# ibdtia.net
KiCad netlist of a schematic drawn in EAGLE
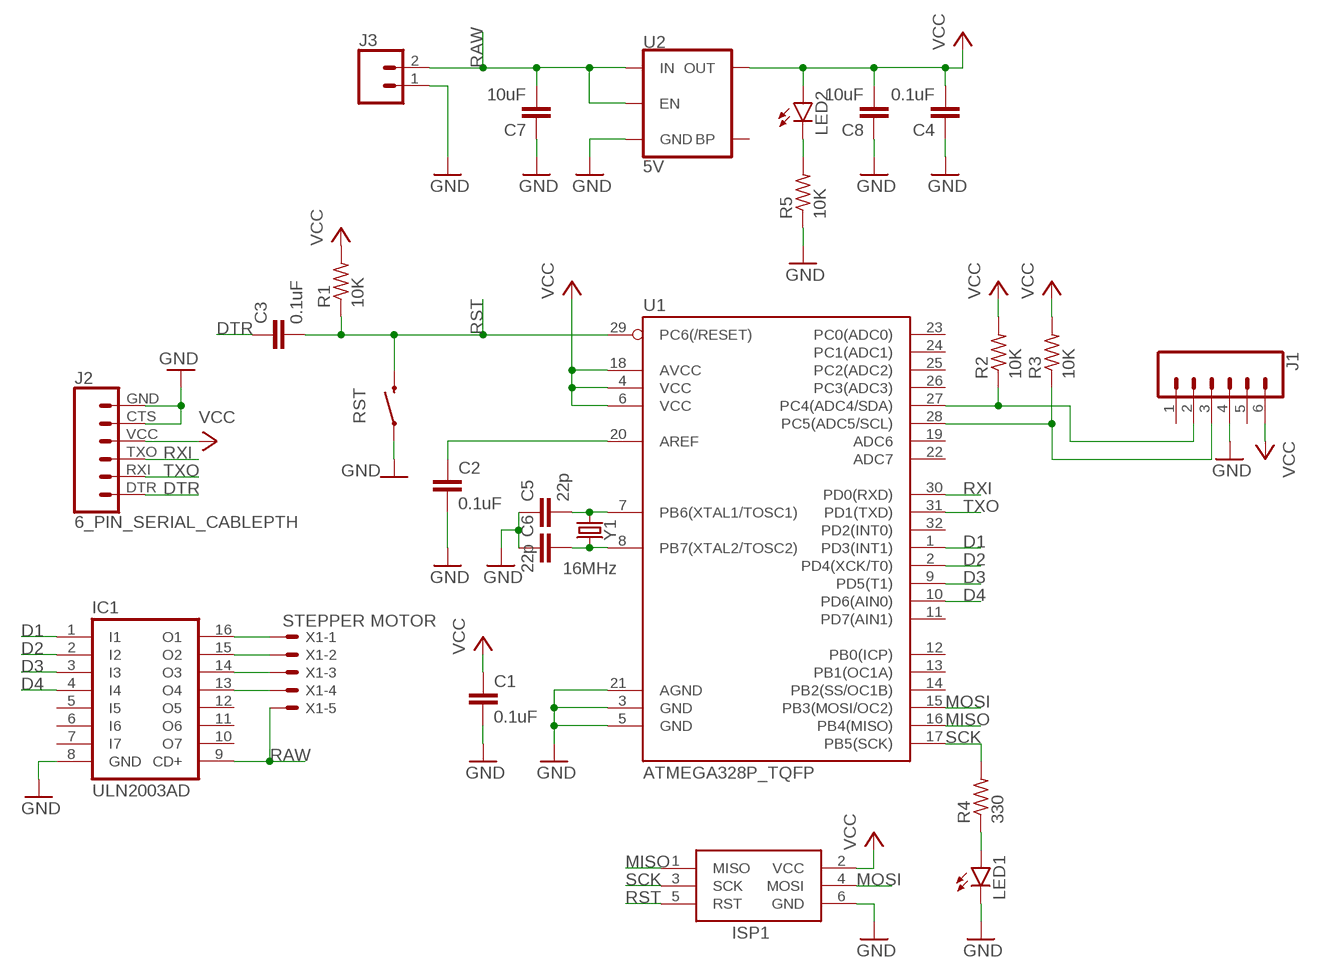
[diagram p0: schematic, sheet 1]

(export (version "E")
  (design (tool "Eeschema 10.0.6"))
  (components
    (comp (ref "C1")
      (value "0.1uF")
      (footprint "eagle-import:C0805")
      (libsource (lib "eagle-import") (part "C-EUC0805"))
    )
    (comp (ref "C2")
      (value "0.1uF")
      (footprint "eagle-import:C0805")
      (libsource (lib "eagle-import") (part "C-EUC0805"))
    )
    (comp (ref "C3")
      (value "0.1uF")
      (footprint "eagle-import:C0805")
      (libsource (lib "eagle-import") (part "C-EUC0805"))
    )
    (comp (ref "C4")
      (value "0.1uF")
      (footprint "eagle-import:C0805")
      (libsource (lib "eagle-import") (part "C-EUC0805"))
    )
    (comp (ref "C5")
      (value "22p")
      (footprint "eagle-import:C0805")
      (libsource (lib "eagle-import") (part "C-EUC0805"))
    )
    (comp (ref "C6")
      (value "22p")
      (footprint "eagle-import:C0805")
      (libsource (lib "eagle-import") (part "C-EUC0805"))
    )
    (comp (ref "C7")
      (value "10uF")
      (footprint "eagle-import:C0805")
      (libsource (lib "eagle-import") (part "C-EUC0805"))
    )
    (comp (ref "C8")
      (value "10uF")
      (footprint "eagle-import:C0805")
      (libsource (lib "eagle-import") (part "C-EUC0805"))
    )
    (comp (ref "IC1")
      (value "ULN2003AD")
      (footprint "eagle-import:SO16")
      (libsource (lib "eagle-import") (part "ULN2003AD"))
    )
    (comp (ref "ISP1")
      (value "AVRISP-6")
      (footprint "eagle-import:AVRISP")
      (libsource (lib "eagle-import") (part "AVRISP-6"))
    )
    (comp (ref "J1")
      (value "CONN_06NO_SILK_FEMALE_PTH")
      (footprint "eagle-import:1X06_NO_SILK")
      (libsource (lib "eagle-import") (part "CONN_06NO_SILK_FEMALE_PTH"))
    )
    (comp (ref "J2")
      (value "6_PIN_SERIAL_CABLEPTH")
      (footprint "eagle-import:FTDI_BASIC")
      (libsource (lib "eagle-import") (part "6_PIN_SERIAL_CABLEPTH"))
    )
    (comp (ref "J3")
      (value "CONN_02")
      (footprint "eagle-import:1X02")
      (libsource (lib "eagle-import") (part "CONN_02"))
    )
    (comp (ref "LED1")
      (value "LEDCHIP-LED0805")
      (footprint "eagle-import:CHIP-LED0805")
      (libsource (lib "eagle-import") (part "LEDCHIP-LED0805"))
    )
    (comp (ref "LED2")
      (value "LEDCHIP-LED0805")
      (footprint "eagle-import:CHIP-LED0805")
      (libsource (lib "eagle-import") (part "LEDCHIP-LED0805"))
    )
    (comp (ref "R1")
      (value "10K")
      (footprint "eagle-import:R0805")
      (libsource (lib "eagle-import") (part "R-US_R0805"))
    )
    (comp (ref "R2")
      (value "10K")
      (footprint "eagle-import:R0805")
      (libsource (lib "eagle-import") (part "R-US_R0805"))
    )
    (comp (ref "R3")
      (value "10K")
      (footprint "eagle-import:R0805")
      (libsource (lib "eagle-import") (part "R-US_R0805"))
    )
    (comp (ref "R4")
      (value "330")
      (footprint "eagle-import:R0805")
      (libsource (lib "eagle-import") (part "R-US_R0805"))
    )
    (comp (ref "R5")
      (value "10K")
      (footprint "eagle-import:R0805")
      (libsource (lib "eagle-import") (part "R-US_R0805"))
    )
    (comp (ref "RST")
      (value "MOMENTARY-SWITCH-SPST-SMD-4.5MM")
      (footprint "eagle-import:TACTILE_SWITCH_SMD_4.5MM")
      (libsource (lib "eagle-import") (part "MOMENTARY-SWITCH-SPST-SMD-4.5MM"))
    )
    (comp (ref "U1")
      (value "ATMEGA328P_TQFP")
      (footprint "eagle-import:TQFP32-08")
      (libsource (lib "eagle-import") (part "ATMEGA328P_TQFP"))
    )
    (comp (ref "U2")
      (value "5V")
      (footprint "eagle-import:SOT23-5")
      (libsource (lib "eagle-import") (part "V_REG_MIC52055V"))
    )
    (comp (ref "X1")
      (value "STEPPER MOTOR")
      (footprint "eagle-import:JST-XH-05-PACKAGE-ROUND-PAD")
      (libsource (lib "eagle-import") (part "JST-XH-05-PIN-ROUND-PAD"))
    )
    (comp (ref "Y1")
      (value "16MHz")
      (footprint "eagle-import:CRYSTAL-SMD-5X3.2-4PAD")
      (libsource (lib "eagle-import") (part "CRYSTAL-16MHZSMD-5X3.2"))
    )
  )
  (nets
    (net (code "1") (name "/D1") (class "Default")
      (node (ref "IC1") (pin "1") (pinfunction "I1_1") (pintype "input"))
      (node (ref "U1") (pin "1") (pinfunction "PD3(INT1)_1") (pintype "bidirectional"))
    )
    (net (code "2") (name "/D2") (class "Default")
      (node (ref "IC1") (pin "2") (pinfunction "I2_2") (pintype "input"))
      (node (ref "U1") (pin "2") (pinfunction "PD4(XCK/T0)_2") (pintype "bidirectional"))
    )
    (net (code "3") (name "/D3") (class "Default")
      (node (ref "IC1") (pin "3") (pinfunction "I3_3") (pintype "input"))
      (node (ref "U1") (pin "9") (pinfunction "PD5(T1)_9") (pintype "bidirectional"))
    )
    (net (code "4") (name "/D4") (class "Default")
      (node (ref "IC1") (pin "4") (pinfunction "I4_4") (pintype "input"))
      (node (ref "U1") (pin "10") (pinfunction "PD6(AIN0)_10") (pintype "bidirectional"))
    )
    (net (code "5") (name "/DTR") (class "Default")
      (node (ref "C3") (pin "1") (pinfunction "1_1") (pintype "passive"))
      (node (ref "J2") (pin "DTR") (pinfunction "1_DTR") (pintype "passive"))
    )
    (net (code "6") (name "/MISO") (class "Default")
      (node (ref "ISP1") (pin "1") (pinfunction "MISO_1") (pintype "input"))
      (node (ref "U1") (pin "16") (pinfunction "PB4(MISO)_16") (pintype "bidirectional"))
    )
    (net (code "7") (name "/MOSI") (class "Default")
      (node (ref "ISP1") (pin "4") (pinfunction "MOSI_4") (pintype "output"))
      (node (ref "U1") (pin "15") (pinfunction "PB3(MOSI/OC2)_15") (pintype "bidirectional"))
    )
    (net (code "8") (name "/RAW") (class "Default")
      (node (ref "C7") (pin "2") (pinfunction "2_2") (pintype "passive"))
      (node (ref "IC1") (pin "9") (pinfunction "CD+_9") (pintype "passive"))
      (node (ref "J3") (pin "2") (pinfunction "2_2") (pintype "passive"))
      (node (ref "U2") (pin "1") (pinfunction "IN_1") (pintype "input"))
      (node (ref "U2") (pin "3") (pinfunction "EN_3") (pintype "input"))
      (node (ref "X1") (pin "5") (pinfunction "S_5") (pintype "passive"))
    )
    (net (code "9") (name "/RST") (class "Default")
      (node (ref "C3") (pin "2") (pinfunction "2_2") (pintype "passive"))
      (node (ref "ISP1") (pin "5") (pinfunction "RST_5") (pintype "output"))
      (node (ref "R1") (pin "1") (pinfunction "1_1") (pintype "passive"))
      (node (ref "RST") (pin "1") (pinfunction "2_1") (pintype "passive"))
      (node (ref "RST") (pin "4") (pinfunction "2_4") (pintype "passive"))
      (node (ref "U1") (pin "29") (pinfunction "PC6(/RESET)_29") (pintype "bidirectional"))
    )
    (net (code "10") (name "/RXI") (class "Default")
      (node (ref "J2") (pin "TXO") (pinfunction "3_TXO") (pintype "passive"))
      (node (ref "U1") (pin "30") (pinfunction "PD0(RXD)_30") (pintype "bidirectional"))
    )
    (net (code "11") (name "/SCK") (class "Default")
      (node (ref "ISP1") (pin "3") (pinfunction "SCK_3") (pintype "output"))
      (node (ref "R4") (pin "2") (pinfunction "2_2") (pintype "passive"))
      (node (ref "U1") (pin "17") (pinfunction "PB5(SCK)_17") (pintype "bidirectional"))
    )
    (net (code "12") (name "/TXO") (class "Default")
      (node (ref "J2") (pin "RXI") (pinfunction "2_RXI") (pintype "passive"))
      (node (ref "U1") (pin "31") (pinfunction "PD1(TXD)_31") (pintype "bidirectional"))
    )
    (net (code "13") (name "GND") (class "Default")
      (node (ref "C1") (pin "2") (pinfunction "2_2") (pintype "passive"))
      (node (ref "C2") (pin "2") (pinfunction "2_2") (pintype "passive"))
      (node (ref "C4") (pin "1") (pinfunction "1_1") (pintype "passive"))
      (node (ref "C5") (pin "1") (pinfunction "1_1") (pintype "passive"))
      (node (ref "C6") (pin "1") (pinfunction "1_1") (pintype "passive"))
      (node (ref "C7") (pin "1") (pinfunction "1_1") (pintype "passive"))
      (node (ref "C8") (pin "1") (pinfunction "1_1") (pintype "passive"))
      (node (ref "IC1") (pin "8") (pinfunction "GND_8") (pintype "power_in"))
      (node (ref "ISP1") (pin "6") (pinfunction "GND_6") (pintype "power_in"))
      (node (ref "J1") (pin "4") (pinfunction "4_4") (pintype "passive"))
      (node (ref "J2") (pin "CTS") (pinfunction "5_CTS") (pintype "passive"))
      (node (ref "J2") (pin "GND") (pinfunction "6_GND") (pintype "passive"))
      (node (ref "J3") (pin "1") (pinfunction "1_1") (pintype "passive"))
      (node (ref "LED1") (pin "C") (pinfunction "C_C") (pintype "passive"))
      (node (ref "R5") (pin "1") (pinfunction "1_1") (pintype "passive"))
      (node (ref "RST") (pin "2") (pinfunction "1_2") (pintype "passive"))
      (node (ref "RST") (pin "3") (pinfunction "1_3") (pintype "passive"))
      (node (ref "U1") (pin "21") (pinfunction "AGND_21") (pintype "bidirectional"))
      (node (ref "U1") (pin "3") (pinfunction "GND_3") (pintype "bidirectional"))
      (node (ref "U1") (pin "5") (pinfunction "GND_5") (pintype "bidirectional"))
      (node (ref "U2") (pin "2") (pinfunction "GND_2") (pintype "input"))
    )
    (net (code "14") (name "Net-(IC1-O1)") (class "Default")
      (node (ref "IC1") (pin "16") (pinfunction "O1_16") (pintype "open_collector"))
      (node (ref "X1") (pin "1") (pinfunction "S_1") (pintype "passive"))
    )
    (net (code "15") (name "Net-(IC1-O2)") (class "Default")
      (node (ref "IC1") (pin "15") (pinfunction "O2_15") (pintype "open_collector"))
      (node (ref "X1") (pin "2") (pinfunction "S_2") (pintype "passive"))
    )
    (net (code "16") (name "Net-(IC1-O3)") (class "Default")
      (node (ref "IC1") (pin "14") (pinfunction "O3_14") (pintype "open_collector"))
      (node (ref "X1") (pin "3") (pinfunction "S_3") (pintype "passive"))
    )
    (net (code "17") (name "Net-(IC1-O4)") (class "Default")
      (node (ref "IC1") (pin "13") (pinfunction "O4_13") (pintype "open_collector"))
      (node (ref "X1") (pin "4") (pinfunction "S_4") (pintype "passive"))
    )
    (net (code "18") (name "Net-(LED1-PadA)") (class "Default")
      (node (ref "LED1") (pin "A") (pinfunction "A_A") (pintype "passive"))
      (node (ref "R4") (pin "1") (pinfunction "1_1") (pintype "passive"))
    )
    (net (code "19") (name "Net-(LED2-PadC)") (class "Default")
      (node (ref "LED2") (pin "C") (pinfunction "C_C") (pintype "passive"))
      (node (ref "R5") (pin "2") (pinfunction "2_2") (pintype "passive"))
    )
    (net (code "20") (name "Net-(U1-AREF)") (class "Default")
      (node (ref "C2") (pin "1") (pinfunction "1_1") (pintype "passive"))
      (node (ref "U1") (pin "20") (pinfunction "AREF_20") (pintype "bidirectional"))
    )
    (net (code "21") (name "Net-(U1-PB6(XTAL1{slash}TOSC1))") (class "Default")
      (node (ref "C5") (pin "2") (pinfunction "2_2") (pintype "passive"))
      (node (ref "U1") (pin "7") (pinfunction "PB6(XTAL1/TOSC1)_7") (pintype "bidirectional"))
      (node (ref "Y1") (pin "1") (pinfunction "1_1") (pintype "passive"))
    )
    (net (code "22") (name "Net-(U1-PB7(XTAL2{slash}TOSC2))") (class "Default")
      (node (ref "C6") (pin "2") (pinfunction "2_2") (pintype "passive"))
      (node (ref "U1") (pin "8") (pinfunction "PB7(XTAL2/TOSC2)_8") (pintype "bidirectional"))
      (node (ref "Y1") (pin "3") (pinfunction "2_3") (pintype "passive"))
    )
    (net (code "23") (name "Net-(U1-PC4(ADC4{slash}SDA))") (class "Default")
      (node (ref "J1") (pin "2") (pinfunction "2_2") (pintype "passive"))
      (node (ref "R2") (pin "1") (pinfunction "1_1") (pintype "passive"))
      (node (ref "U1") (pin "27") (pinfunction "PC4(ADC4/SDA)_27") (pintype "bidirectional"))
    )
    (net (code "24") (name "Net-(U1-PC5(ADC5{slash}SCL))") (class "Default")
      (node (ref "J1") (pin "3") (pinfunction "3_3") (pintype "passive"))
      (node (ref "R3") (pin "1") (pinfunction "1_1") (pintype "passive"))
      (node (ref "U1") (pin "28") (pinfunction "PC5(ADC5/SCL)_28") (pintype "bidirectional"))
    )
    (net (code "25") (name "VCC") (class "Default")
      (node (ref "C1") (pin "1") (pinfunction "1_1") (pintype "passive"))
      (node (ref "C4") (pin "2") (pinfunction "2_2") (pintype "passive"))
      (node (ref "C8") (pin "2") (pinfunction "2_2") (pintype "passive"))
      (node (ref "ISP1") (pin "2") (pinfunction "VCC_2") (pintype "power_in"))
      (node (ref "J1") (pin "6") (pinfunction "6_6") (pintype "passive"))
      (node (ref "J2") (pin "VCC") (pinfunction "4_VCC") (pintype "passive"))
      (node (ref "LED2") (pin "A") (pinfunction "A_A") (pintype "passive"))
      (node (ref "R1") (pin "2") (pinfunction "2_2") (pintype "passive"))
      (node (ref "R2") (pin "2") (pinfunction "2_2") (pintype "passive"))
      (node (ref "R3") (pin "2") (pinfunction "2_2") (pintype "passive"))
      (node (ref "U1") (pin "18") (pinfunction "AVCC_18") (pintype "bidirectional"))
      (node (ref "U1") (pin "4") (pinfunction "VCC_4") (pintype "bidirectional"))
      (node (ref "U1") (pin "6") (pinfunction "VCC_6") (pintype "bidirectional"))
      (node (ref "U2") (pin "5") (pinfunction "OUT_5") (pintype "passive"))
    )
    (net (code "26") (name "unconnected-(IC1-I5-Pad5)") (class "Default")
      (node (ref "IC1") (pin "5") (pinfunction "I5_5") (pintype "input"))
    )
    (net (code "27") (name "unconnected-(IC1-I6-Pad6)") (class "Default")
      (node (ref "IC1") (pin "6") (pinfunction "I6_6") (pintype "input"))
    )
    (net (code "28") (name "unconnected-(IC1-I7-Pad7)") (class "Default")
      (node (ref "IC1") (pin "7") (pinfunction "I7_7") (pintype "input"))
    )
    (net (code "29") (name "unconnected-(IC1-O5-Pad12)") (class "Default")
      (node (ref "IC1") (pin "12") (pinfunction "O5_12") (pintype "open_collector"))
    )
    (net (code "30") (name "unconnected-(IC1-O6-Pad11)") (class "Default")
      (node (ref "IC1") (pin "11") (pinfunction "O6_11") (pintype "open_collector"))
    )
    (net (code "31") (name "unconnected-(IC1-O7-Pad10)") (class "Default")
      (node (ref "IC1") (pin "10") (pinfunction "O7_10") (pintype "open_collector"))
    )
    (net (code "32") (name "unconnected-(J1-Pad1)") (class "Default")
      (node (ref "J1") (pin "1") (pinfunction "1_1") (pintype "passive"))
    )
    (net (code "33") (name "unconnected-(J1-Pad5)") (class "Default")
      (node (ref "J1") (pin "5") (pinfunction "5_5") (pintype "passive"))
    )
    (net (code "34") (name "unconnected-(U1-ADC6-Pad19)") (class "Default")
      (node (ref "U1") (pin "19") (pinfunction "ADC6_19") (pintype "bidirectional"))
    )
    (net (code "35") (name "unconnected-(U1-ADC7-Pad22)") (class "Default")
      (node (ref "U1") (pin "22") (pinfunction "ADC7_22") (pintype "bidirectional"))
    )
    (net (code "36") (name "unconnected-(U1-PB0(ICP)-Pad12)") (class "Default")
      (node (ref "U1") (pin "12") (pinfunction "PB0(ICP)_12") (pintype "bidirectional"))
    )
    (net (code "37") (name "unconnected-(U1-PB1(OC1A)-Pad13)") (class "Default")
      (node (ref "U1") (pin "13") (pinfunction "PB1(OC1A)_13") (pintype "bidirectional"))
    )
    (net (code "38") (name "unconnected-(U1-PB2(SS{slash}OC1B)-Pad14)") (class "Default")
      (node (ref "U1") (pin "14") (pinfunction "PB2(SS/OC1B)_14") (pintype "bidirectional"))
    )
    (net (code "39") (name "unconnected-(U1-PC0(ADC0)-Pad23)") (class "Default")
      (node (ref "U1") (pin "23") (pinfunction "PC0(ADC0)_23") (pintype "bidirectional"))
    )
    (net (code "40") (name "unconnected-(U1-PC1(ADC1)-Pad24)") (class "Default")
      (node (ref "U1") (pin "24") (pinfunction "PC1(ADC1)_24") (pintype "bidirectional"))
    )
    (net (code "41") (name "unconnected-(U1-PC2(ADC2)-Pad25)") (class "Default")
      (node (ref "U1") (pin "25") (pinfunction "PC2(ADC2)_25") (pintype "bidirectional"))
    )
    (net (code "42") (name "unconnected-(U1-PC3(ADC3)-Pad26)") (class "Default")
      (node (ref "U1") (pin "26") (pinfunction "PC3(ADC3)_26") (pintype "bidirectional"))
    )
    (net (code "43") (name "unconnected-(U1-PD2(INT0)-Pad32)") (class "Default")
      (node (ref "U1") (pin "32") (pinfunction "PD2(INT0)_32") (pintype "bidirectional"))
    )
    (net (code "44") (name "unconnected-(U1-PD7(AIN1)-Pad11)") (class "Default")
      (node (ref "U1") (pin "11") (pinfunction "PD7(AIN1)_11") (pintype "bidirectional"))
    )
    (net (code "45") (name "unconnected-(U2-BP-Pad4)") (class "Default")
      (node (ref "U2") (pin "4") (pinfunction "BP_4") (pintype "input"))
    )
  )
)
